# Debounce_Filter.net
KiCad netlist of a schematic drawn in Altium Designer
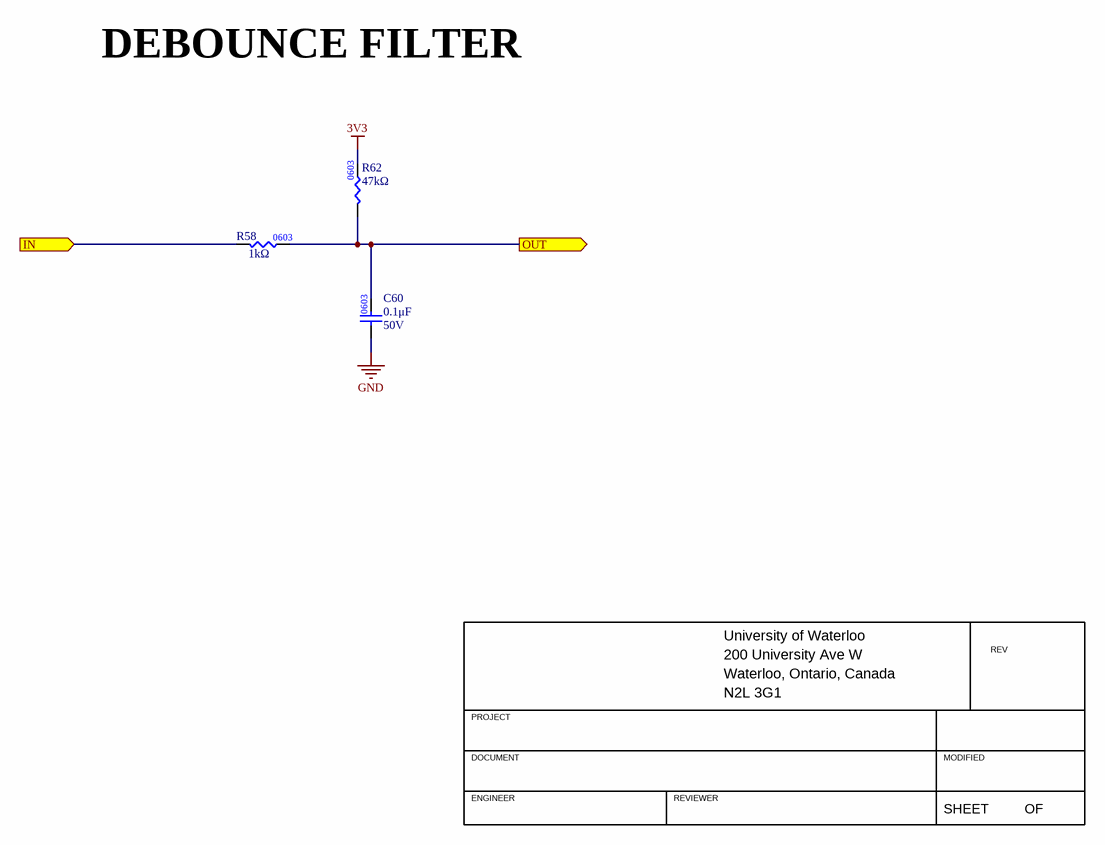
[diagram p0: Debounce Filter.SchDoc]

(export (version "E")
  (design (tool "Eeschema 10.0.6"))
  (components
    (comp (ref "C60")
      (value "0.1μF")
      (footprint "CAP0603")
      (description "CAP CER 0.1UF 50V X7R 0603")
      (fields (field (name "VOLTAGE RATING") "50V") (field (name "Comment") "CAP_0.1uF_50V_0603"))
      (libsource (lib "Personal_Schematic_Library_2022") (part "CAP_0.1uF_50V_0603"))
    )
    (comp (ref "R58")
      (value "1kΩ")
      (footprint "RES0603")
      (description "RES 1K OHM 1% 1/8W 0603")
      (fields (field (name "Comment") "RES_1kΩ_0603_1%"))
      (libsource (lib "Personal_Schematic_Library_2022") (part "RES_1kΩ_0603_1%"))
    )
    (comp (ref "R62")
      (value "47kΩ")
      (footprint "RES0603")
      (description "RES 47K OHM 1% 1/10W 0603")
      (fields (field (name "Comment") "RES_47kΩ_0603_1%"))
      (libsource (lib "Personal_Schematic_Library_2022") (part "RES_47kΩ_0603_1%"))
    )
  )
  (nets
    (net (code "1") (name "/IN") (class "Default")
      (node (ref "R58") (pin "1") (pinfunction "1_1") (pintype "passive"))
    )
    (net (code "2") (name "/OUT") (class "Default")
      (node (ref "C60") (pin "2") (pinfunction "2_2") (pintype "passive"))
      (node (ref "R58") (pin "2") (pinfunction "2_2") (pintype "passive"))
      (node (ref "R62") (pin "1") (pinfunction "1_1") (pintype "passive"))
    )
    (net (code "3") (name "3V3") (class "Default")
      (node (ref "R62") (pin "2") (pinfunction "2_2") (pintype "passive"))
    )
    (net (code "4") (name "GND") (class "Default")
      (node (ref "C60") (pin "1") (pinfunction "1_1") (pintype "passive"))
    )
  )
)
